# 04_CapTouch.net
KiCad netlist of a schematic drawn in Altium Designer
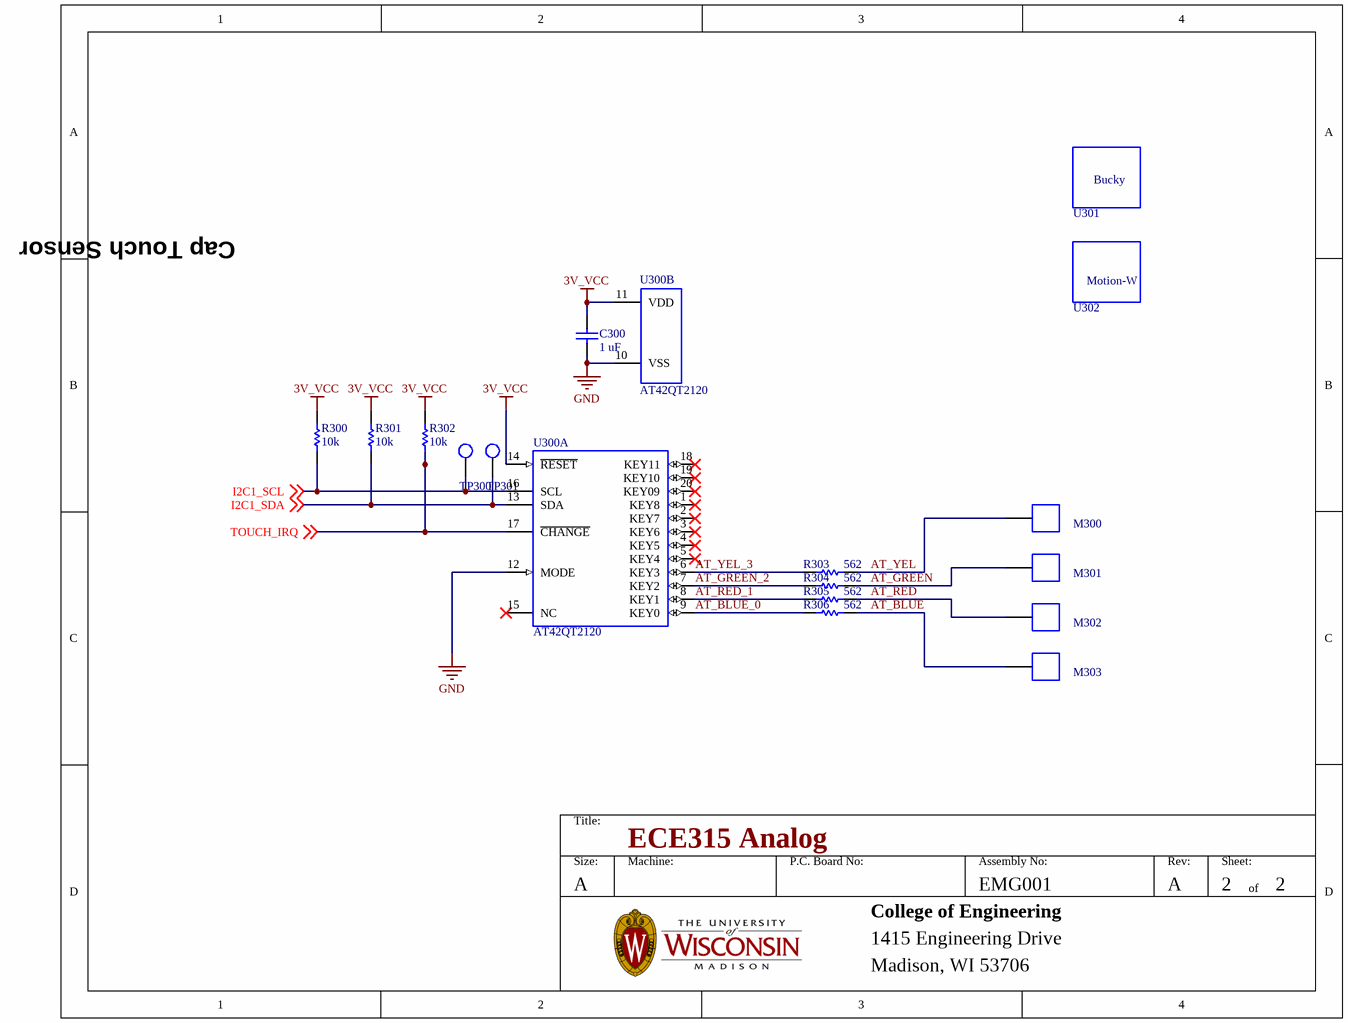
[diagram p0: 04_CapTouch.SchDoc]

(export (version "E")
  (design (tool "Eeschema 10.0.6"))
  (components
    (comp (ref "C300")
      (value "CAP_0805_U_001.00")
      (footprint "CAP_0805")
      (description "CAP CER 1UF 16V 10% X7R 0805")
      (fields
        (field (name "TOLERANCE") "10 %")
        (field (name "MANUFACTURER") "Kemet")
        (field (name "CAPACITANCE") "1 uF")
      )
      (libsource (lib "ece315-2017-fall") (part "CAP_0805_U_001.00"))
    )
    (comp (ref "M300")
      (value "Mech_TouchPad")
      (footprint "TouchPad")
      (description "Capacative Touch Sensor Pad")
      (libsource (lib "ece315-2017-fall") (part "Mech_TouchPad"))
    )
    (comp (ref "M301")
      (value "Mech_TouchPad")
      (footprint "TouchPad")
      (description "Capacative Touch Sensor Pad")
      (libsource (lib "ece315-2017-fall") (part "Mech_TouchPad"))
    )
    (comp (ref "M302")
      (value "Mech_TouchPad")
      (footprint "TouchPad")
      (description "Capacative Touch Sensor Pad")
      (libsource (lib "ece315-2017-fall") (part "Mech_TouchPad"))
    )
    (comp (ref "M303")
      (value "Mech_TouchPad")
      (footprint "TouchPad")
      (description "Capacative Touch Sensor Pad")
      (libsource (lib "ece315-2017-fall") (part "Mech_TouchPad"))
    )
    (comp (ref "R300")
      (value "10K")
      (description "RES SMD 10K OHM 1% 1/8W 0805")
      (fields
        (field (name "MANUFACTURER PART NUMBER") "ERJ-6ENF1002V")
        (field (name "MANUFACTURER") "Panasonic / Panasonic ECG")
        (field (name "RESISTANCE") "10k")
      )
      (libsource (lib "ece315-2017-fall") (part "RES_0805_K_010.00"))
    )
    (comp (ref "R301")
      (value "10K")
      (description "RES SMD 10K OHM 1% 1/8W 0805")
      (fields
        (field (name "MANUFACTURER PART NUMBER") "ERJ-6ENF1002V")
        (field (name "MANUFACTURER") "Panasonic / Panasonic ECG")
        (field (name "RESISTANCE") "10k")
      )
      (libsource (lib "ece315-2017-fall") (part "RES_0805_K_010.00"))
    )
    (comp (ref "R302")
      (value "10K")
      (description "RES SMD 10K OHM 1% 1/8W 0805")
      (fields
        (field (name "MANUFACTURER PART NUMBER") "ERJ-6ENF1002V")
        (field (name "MANUFACTURER") "Panasonic / Panasonic ECG")
        (field (name "RESISTANCE") "10k")
      )
      (libsource (lib "ece315-2017-fall") (part "RES_0805_K_010.00"))
    )
    (comp (ref "R303")
      (value "RES_0805_R_562_00")
      (footprint "RES_0805")
      (description "RES SMD 562 OHM 1% 1/8W 0805")
      (fields
        (field (name "MANUFACTURER") "Panasonic / Panasonic ECG")
        (field (name "MANUFACTURER PART NUMBER") "ERJ-6ENF5620V")
        (field (name "RESISTANCE (OHMS)") "562")
      )
      (libsource (lib "ece315-2017-fall") (part "RES_0805_R_562_00"))
    )
    (comp (ref "R304")
      (value "RES_0805_R_562_00")
      (footprint "RES_0805")
      (description "RES SMD 562 OHM 1% 1/8W 0805")
      (fields
        (field (name "MANUFACTURER") "Panasonic / Panasonic ECG")
        (field (name "MANUFACTURER PART NUMBER") "ERJ-6ENF5620V")
        (field (name "RESISTANCE (OHMS)") "562")
      )
      (libsource (lib "ece315-2017-fall") (part "RES_0805_R_562_00"))
    )
    (comp (ref "R305")
      (value "RES_0805_R_562_00")
      (footprint "RES_0805")
      (description "RES SMD 562 OHM 1% 1/8W 0805")
      (fields
        (field (name "MANUFACTURER") "Panasonic / Panasonic ECG")
        (field (name "MANUFACTURER PART NUMBER") "ERJ-6ENF5620V")
        (field (name "RESISTANCE (OHMS)") "562")
      )
      (libsource (lib "ece315-2017-fall") (part "RES_0805_R_562_00"))
    )
    (comp (ref "R306")
      (value "RES_0805_R_562_00")
      (footprint "RES_0805")
      (description "RES SMD 562 OHM 1% 1/8W 0805")
      (fields
        (field (name "MANUFACTURER") "Panasonic / Panasonic ECG")
        (field (name "MANUFACTURER PART NUMBER") "ERJ-6ENF5620V")
        (field (name "RESISTANCE (OHMS)") "562")
      )
      (libsource (lib "ece315-2017-fall") (part "RES_0805_R_562_00"))
    )
    (comp (ref "TP300")
      (value "TP_1206")
      (footprint "TP-SMC-1206")
      (description "Test Point SMD 1206")
      (fields
        (field (name "MANUFACTURER") "TE Connectivity (Tyco Electronics)")
        (field (name "MANUFACTURER PART NUMBER") "1625854-1")
      )
      (libsource (lib "ece315-2017-fall") (part "TP_1206"))
    )
    (comp (ref "TP301")
      (value "TP_1206")
      (footprint "TP-SMC-1206")
      (description "Test Point SMD 1206")
      (fields
        (field (name "MANUFACTURER") "TE Connectivity (Tyco Electronics)")
        (field (name "MANUFACTURER PART NUMBER") "1625854-1")
      )
      (libsource (lib "ece315-2017-fall") (part "TP_1206"))
    )
    (comp (ref "U300")
      (value "AT42QT2120")
      (footprint "SOIC127P1030-20M")
      (description "Touch Sensor, Atmel")
      (fields
        (field (name "MANUFACTURER") "Atmel")
        (field (name "MANUFACTURER PART NUMBER") "AT42QT2120-SUR")
      )
      (libsource (lib "ece315-2017-fall") (part "IC_AT42QT2120"))
    )
    (comp (ref "U301")
      (value "Bucky")
      (footprint "BuckyBadger")
      (description "Bucky Badger Image")
      (fields (field (name "MANUFACTURER PART NUMBER") "UW Bucky"))
      (libsource (lib "ece315-2017-fall") (part "Bucky"))
    )
    (comp (ref "U302")
      (value "Motion_W")
      (footprint "Motion_W")
      (description "Motion W Image")
      (fields (field (name "MANUFACTURER PART NUMBER") "UW Bucky"))
      (libsource (lib "ece315-2017-fall") (part "Motion_W"))
    )
  )
  (nets
    (net (code "1") (name "/AT_BLUE") (class "Default")
      (node (ref "M303") (pin "1") (pinfunction "1_1") (pintype "passive"))
      (node (ref "R306") (pin "2") (pinfunction "2_2") (pintype "passive"))
    )
    (net (code "2") (name "/AT_BLUE_0") (class "Default")
      (node (ref "R306") (pin "1") (pinfunction "1_1") (pintype "passive"))
      (node (ref "U300") (pin "9") (pinfunction "KEY0_9") (pintype "bidirectional"))
    )
    (net (code "3") (name "/AT_GREEN") (class "Default")
      (node (ref "M301") (pin "1") (pinfunction "1_1") (pintype "passive"))
      (node (ref "R304") (pin "2") (pinfunction "2_2") (pintype "passive"))
    )
    (net (code "4") (name "/AT_GREEN_2") (class "Default")
      (node (ref "R304") (pin "1") (pinfunction "1_1") (pintype "passive"))
      (node (ref "U300") (pin "7") (pinfunction "KEY2_7") (pintype "bidirectional"))
    )
    (net (code "5") (name "/AT_RED") (class "Default")
      (node (ref "M302") (pin "1") (pinfunction "1_1") (pintype "passive"))
      (node (ref "R305") (pin "2") (pinfunction "2_2") (pintype "passive"))
    )
    (net (code "6") (name "/AT_RED_1") (class "Default")
      (node (ref "R305") (pin "1") (pinfunction "1_1") (pintype "passive"))
      (node (ref "U300") (pin "8") (pinfunction "KEY1_8") (pintype "bidirectional"))
    )
    (net (code "7") (name "/AT_YEL") (class "Default")
      (node (ref "M300") (pin "1") (pinfunction "1_1") (pintype "passive"))
      (node (ref "R303") (pin "2") (pinfunction "2_2") (pintype "passive"))
    )
    (net (code "8") (name "/AT_YEL_3") (class "Default")
      (node (ref "R303") (pin "1") (pinfunction "1_1") (pintype "passive"))
      (node (ref "U300") (pin "6") (pinfunction "KEY3_6") (pintype "bidirectional"))
    )
    (net (code "9") (name "3V_VCC") (class "Default")
      (node (ref "C300") (pin "1") (pinfunction "1_1") (pintype "passive"))
      (node (ref "R300") (pin "2") (pinfunction "2_2") (pintype "passive"))
      (node (ref "R301") (pin "2") (pinfunction "2_2") (pintype "passive"))
      (node (ref "R302") (pin "2") (pinfunction "2_2") (pintype "passive"))
      (node (ref "U300") (pin "11") (pinfunction "VDD_11") (pintype "power_in"))
      (node (ref "U300") (pin "14") (pinfunction "~{RESET}_14") (pintype "input"))
    )
    (net (code "10") (name "GND") (class "Default")
      (node (ref "C300") (pin "2") (pinfunction "2_2") (pintype "passive"))
      (node (ref "U300") (pin "10") (pinfunction "VSS_10") (pintype "power_in"))
      (node (ref "U300") (pin "12") (pinfunction "MODE_12") (pintype "input"))
    )
    (net (code "11") (name "I2C1_SCL") (class "Default")
      (node (ref "R300") (pin "1") (pinfunction "1_1") (pintype "passive"))
      (node (ref "TP300") (pin "1") (pintype "passive"))
      (node (ref "U300") (pin "16") (pinfunction "SCL_16") (pintype "open_collector"))
    )
    (net (code "12") (name "I2C1_SDA") (class "Default")
      (node (ref "R301") (pin "1") (pinfunction "1_1") (pintype "passive"))
      (node (ref "TP301") (pin "1") (pintype "passive"))
      (node (ref "U300") (pin "13") (pinfunction "SDA_13") (pintype "open_collector"))
    )
    (net (code "13") (name "TOUCH_IRQ") (class "Default")
      (node (ref "R302") (pin "1") (pinfunction "1_1") (pintype "passive"))
      (node (ref "U300") (pin "17") (pinfunction "~{CHANGE}_17") (pintype "open_collector"))
    )
    (net (code "14") (name "unconnected-(U300A-KEY4-Pad5)") (class "Default")
      (node (ref "U300") (pin "5") (pinfunction "KEY4_5") (pintype "bidirectional+no_connect"))
    )
    (net (code "15") (name "unconnected-(U300A-KEY5-Pad4)") (class "Default")
      (node (ref "U300") (pin "4") (pinfunction "KEY5_4") (pintype "bidirectional+no_connect"))
    )
    (net (code "16") (name "unconnected-(U300A-KEY6-Pad3)") (class "Default")
      (node (ref "U300") (pin "3") (pinfunction "KEY6_3") (pintype "bidirectional+no_connect"))
    )
    (net (code "17") (name "unconnected-(U300A-KEY7-Pad2)") (class "Default")
      (node (ref "U300") (pin "2") (pinfunction "KEY7_2") (pintype "bidirectional+no_connect"))
    )
    (net (code "18") (name "unconnected-(U300A-KEY8-Pad1)") (class "Default")
      (node (ref "U300") (pin "1") (pinfunction "KEY8_1") (pintype "bidirectional+no_connect"))
    )
    (net (code "19") (name "unconnected-(U300A-KEY09-Pad20)") (class "Default")
      (node (ref "U300") (pin "20") (pinfunction "KEY09_20") (pintype "bidirectional+no_connect"))
    )
    (net (code "20") (name "unconnected-(U300A-KEY10-Pad19)") (class "Default")
      (node (ref "U300") (pin "19") (pinfunction "KEY10_19") (pintype "bidirectional+no_connect"))
    )
    (net (code "21") (name "unconnected-(U300A-KEY11-Pad18)") (class "Default")
      (node (ref "U300") (pin "18") (pinfunction "KEY11_18") (pintype "bidirectional+no_connect"))
    )
    (net (code "22") (name "unconnected-(U300A-NC-Pad15)") (class "Default")
      (node (ref "U300") (pin "15") (pinfunction "NC_15") (pintype "passive+no_connect"))
    )
  )
)
